# PROM.net
KiCad netlist of a schematic drawn in Altium Designer
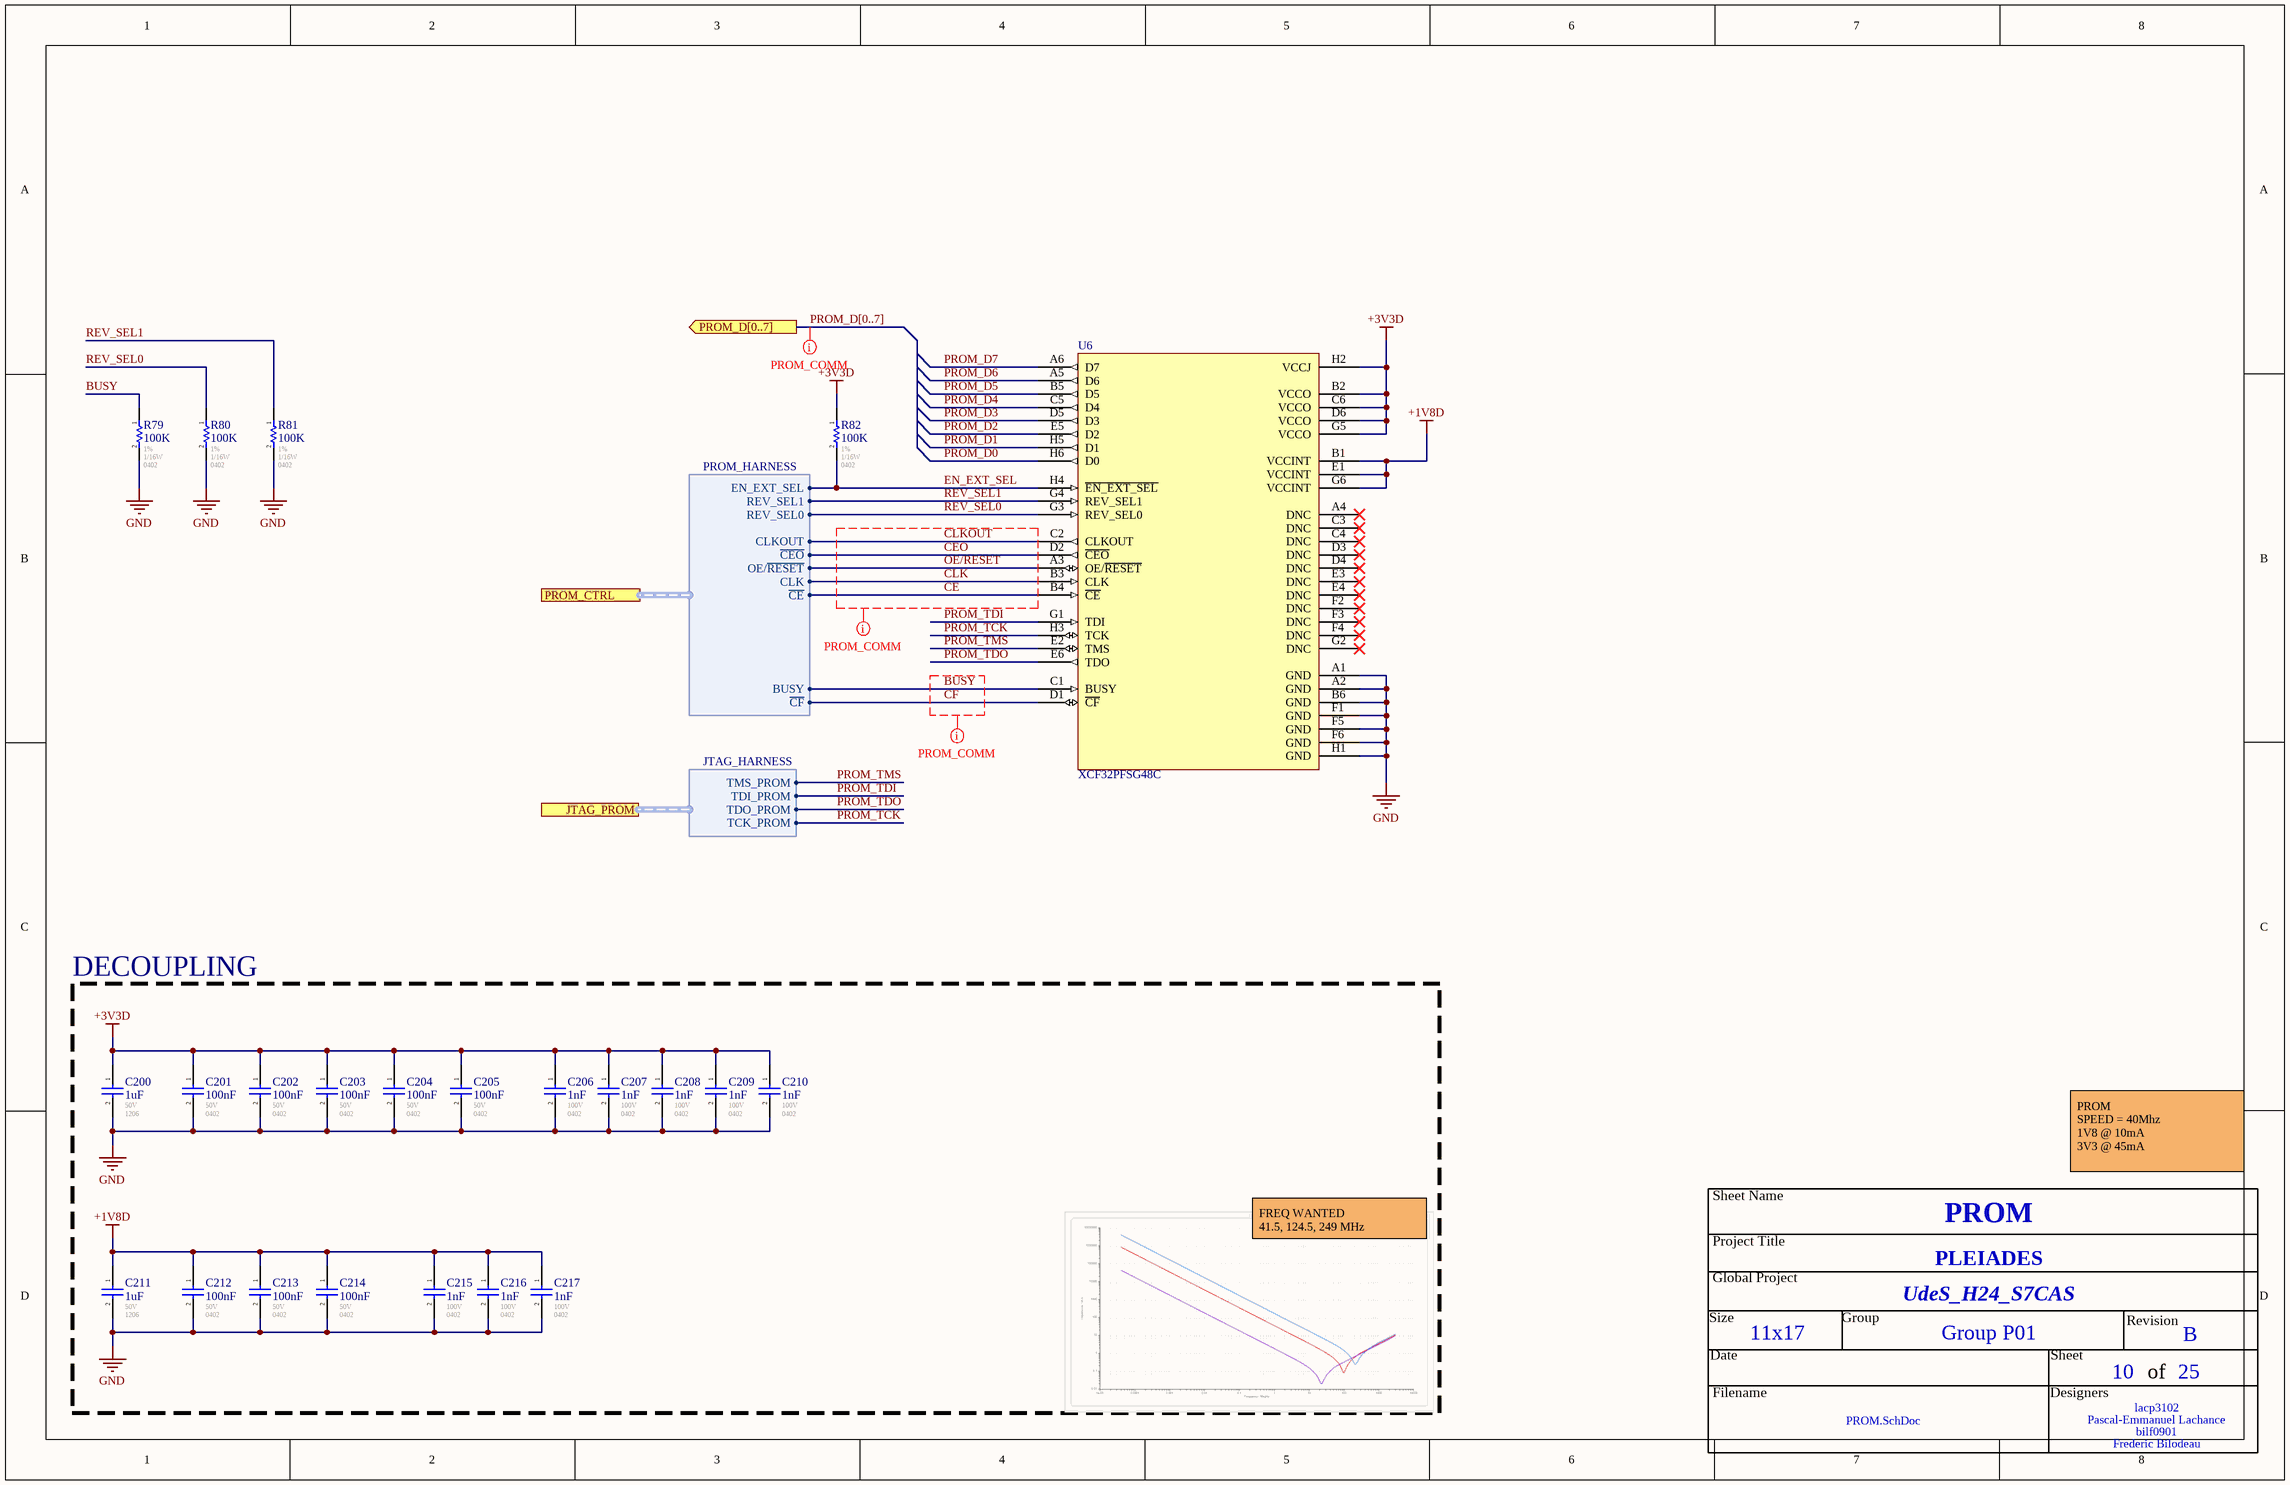
[diagram p0: PROM.SchDoc]

(export (version "E")
  (design (tool "Eeschema 10.0.6"))
  (components
    (comp (ref "C200")
      (value "1uF")
      (footprint "1206")
      (description "GCJ31CR71H105KA12L\r\n1206 1uF 10% X7R Ceramic Capacitor")
      (fields
        (field (name "MFR") "Murata")
        (field (name "PART#") "GCJ31CR71H105KA12L")
        (field (name "VOLTAGE - RATED") "50V")
      )
      (libsource (lib "Symbols") (part "CAP_CER"))
    )
    (comp (ref "C201")
      (value "100nF")
      (footprint "0402")
      (description "GCM155R71H104KE02J\r\n0402 100nF 10% X7R Ceramic Capacitor")
      (fields
        (field (name "MFR") "Murata")
        (field (name "PART#") "GCM155R71H104KE02J")
        (field (name "VOLTAGE - RATED") "50V")
      )
      (libsource (lib "Symbols") (part "CAP_CER"))
    )
    (comp (ref "C202")
      (value "100nF")
      (footprint "0402")
      (description "GCM155R71H104KE02J\r\n0402 100nF 10% X7R Ceramic Capacitor")
      (fields
        (field (name "MFR") "Murata")
        (field (name "PART#") "GCM155R71H104KE02J")
        (field (name "VOLTAGE - RATED") "50V")
      )
      (libsource (lib "Symbols") (part "CAP_CER"))
    )
    (comp (ref "C203")
      (value "100nF")
      (footprint "0402")
      (description "GCM155R71H104KE02J\r\n0402 100nF 10% X7R Ceramic Capacitor")
      (fields
        (field (name "MFR") "Murata")
        (field (name "PART#") "GCM155R71H104KE02J")
        (field (name "VOLTAGE - RATED") "50V")
      )
      (libsource (lib "Symbols") (part "CAP_CER"))
    )
    (comp (ref "C204")
      (value "100nF")
      (footprint "0402")
      (description "GCM155R71H104KE02J\r\n0402 100nF 10% X7R Ceramic Capacitor")
      (fields
        (field (name "MFR") "Murata")
        (field (name "PART#") "GCM155R71H104KE02J")
        (field (name "VOLTAGE - RATED") "50V")
      )
      (libsource (lib "Symbols") (part "CAP_CER"))
    )
    (comp (ref "C205")
      (value "100nF")
      (footprint "0402")
      (description "GCM155R71H104KE02J\r\n0402 100nF 10% X7R Ceramic Capacitor")
      (fields
        (field (name "MFR") "Murata")
        (field (name "PART#") "GCM155R71H104KE02J")
        (field (name "VOLTAGE - RATED") "50V")
      )
      (libsource (lib "Symbols") (part "CAP_CER"))
    )
    (comp (ref "C206")
      (value "1nF")
      (footprint "0402")
      (description "GCM155R72A102KA37D\r\n0402 1nF 10% X7R Ceramic Capacitor")
      (fields
        (field (name "MFR") "Murata")
        (field (name "PART#") "GCM155R72A102KA37D")
        (field (name "VOLTAGE - RATED") "100V")
      )
      (libsource (lib "Symbols") (part "CAP_CER"))
    )
    (comp (ref "C207")
      (value "1nF")
      (footprint "0402")
      (description "GCM155R72A102KA37D\r\n0402 1nF 10% X7R Ceramic Capacitor")
      (fields
        (field (name "MFR") "Murata")
        (field (name "PART#") "GCM155R72A102KA37D")
        (field (name "VOLTAGE - RATED") "100V")
      )
      (libsource (lib "Symbols") (part "CAP_CER"))
    )
    (comp (ref "C208")
      (value "1nF")
      (footprint "0402")
      (description "GCM155R72A102KA37D\r\n0402 1nF 10% X7R Ceramic Capacitor")
      (fields
        (field (name "MFR") "Murata")
        (field (name "PART#") "GCM155R72A102KA37D")
        (field (name "VOLTAGE - RATED") "100V")
      )
      (libsource (lib "Symbols") (part "CAP_CER"))
    )
    (comp (ref "C209")
      (value "1nF")
      (footprint "0402")
      (description "GCM155R72A102KA37D\r\n0402 1nF 10% X7R Ceramic Capacitor")
      (fields
        (field (name "MFR") "Murata")
        (field (name "PART#") "GCM155R72A102KA37D")
        (field (name "VOLTAGE - RATED") "100V")
      )
      (libsource (lib "Symbols") (part "CAP_CER"))
    )
    (comp (ref "C210")
      (value "1nF")
      (footprint "0402")
      (description "GCM155R72A102KA37D\r\n0402 1nF 10% X7R Ceramic Capacitor")
      (fields
        (field (name "MFR") "Murata")
        (field (name "PART#") "GCM155R72A102KA37D")
        (field (name "VOLTAGE - RATED") "100V")
      )
      (libsource (lib "Symbols") (part "CAP_CER"))
    )
    (comp (ref "C211")
      (value "1uF")
      (footprint "1206")
      (description "GCJ31CR71H105KA12L\r\n1206 1uF 10% X7R Ceramic Capacitor")
      (fields
        (field (name "MFR") "Murata")
        (field (name "PART#") "GCJ31CR71H105KA12L")
        (field (name "VOLTAGE - RATED") "50V")
      )
      (libsource (lib "Symbols") (part "CAP_CER"))
    )
    (comp (ref "C212")
      (value "100nF")
      (footprint "0402")
      (description "GCM155R71H104KE02J\r\n0402 100nF 10% X7R Ceramic Capacitor")
      (fields
        (field (name "MFR") "Murata")
        (field (name "PART#") "GCM155R71H104KE02J")
        (field (name "VOLTAGE - RATED") "50V")
      )
      (libsource (lib "Symbols") (part "CAP_CER"))
    )
    (comp (ref "C213")
      (value "100nF")
      (footprint "0402")
      (description "GCM155R71H104KE02J\r\n0402 100nF 10% X7R Ceramic Capacitor")
      (fields
        (field (name "MFR") "Murata")
        (field (name "PART#") "GCM155R71H104KE02J")
        (field (name "VOLTAGE - RATED") "50V")
      )
      (libsource (lib "Symbols") (part "CAP_CER"))
    )
    (comp (ref "C214")
      (value "100nF")
      (footprint "0402")
      (description "GCM155R71H104KE02J\r\n0402 100nF 10% X7R Ceramic Capacitor")
      (fields
        (field (name "MFR") "Murata")
        (field (name "PART#") "GCM155R71H104KE02J")
        (field (name "VOLTAGE - RATED") "50V")
      )
      (libsource (lib "Symbols") (part "CAP_CER"))
    )
    (comp (ref "C215")
      (value "1nF")
      (footprint "0402")
      (description "GCM155R72A102KA37D\r\n0402 1nF 10% X7R Ceramic Capacitor")
      (fields
        (field (name "MFR") "Murata")
        (field (name "PART#") "GCM155R72A102KA37D")
        (field (name "VOLTAGE - RATED") "100V")
      )
      (libsource (lib "Symbols") (part "CAP_CER"))
    )
    (comp (ref "C216")
      (value "1nF")
      (footprint "0402")
      (description "GCM155R72A102KA37D\r\n0402 1nF 10% X7R Ceramic Capacitor")
      (fields
        (field (name "MFR") "Murata")
        (field (name "PART#") "GCM155R72A102KA37D")
        (field (name "VOLTAGE - RATED") "100V")
      )
      (libsource (lib "Symbols") (part "CAP_CER"))
    )
    (comp (ref "C217")
      (value "1nF")
      (footprint "0402")
      (description "GCM155R72A102KA37D\r\n0402 1nF 10% X7R Ceramic Capacitor")
      (fields
        (field (name "MFR") "Murata")
        (field (name "PART#") "GCM155R72A102KA37D")
        (field (name "VOLTAGE - RATED") "100V")
      )
      (libsource (lib "Symbols") (part "CAP_CER"))
    )
    (comp (ref "R79")
      (value "100K")
      (footprint "RES_0402")
      (fields
        (field (name "TOLERANCE") "1%")
        (field (name "POWER") "1/16W")
        (field (name "PACKAGE / CASE") "0402")
      )
      (libsource (lib "Symbols") (part "RESISTOR"))
    )
    (comp (ref "R80")
      (value "100K")
      (footprint "RES_0402")
      (fields
        (field (name "TOLERANCE") "1%")
        (field (name "POWER") "1/16W")
        (field (name "PACKAGE / CASE") "0402")
      )
      (libsource (lib "Symbols") (part "RESISTOR"))
    )
    (comp (ref "R81")
      (value "100K")
      (footprint "RES_0402")
      (fields
        (field (name "TOLERANCE") "1%")
        (field (name "POWER") "1/16W")
        (field (name "PACKAGE / CASE") "0402")
      )
      (libsource (lib "Symbols") (part "RESISTOR"))
    )
    (comp (ref "R82")
      (value "100K")
      (footprint "RES_0402")
      (fields
        (field (name "TOLERANCE") "1%")
        (field (name "POWER") "1/16W")
        (field (name "PACKAGE / CASE") "0402")
      )
      (libsource (lib "Symbols") (part "RESISTOR"))
    )
    (comp (ref "U6")
      (value "XCF32PFSG48C")
      (footprint "TFBGA-48_0.8MM_8X9")
      (description "IC PROM SRL/PAR 1.8V 32M 48CSBGA")
      (fields (field (name "MFR") "Xilinx"))
      (libsource (lib "Misc") (part "XCF32PFSG48C"))
    )
  )
  (nets
    (net (code "3") (name "+1V8D") (class "Default")
      (node (ref "C211") (pin "1") (pinfunction "1_1") (pintype "passive"))
      (node (ref "C212") (pin "1") (pinfunction "1_1") (pintype "passive"))
      (node (ref "C213") (pin "1") (pinfunction "1_1") (pintype "passive"))
      (node (ref "C214") (pin "1") (pinfunction "1_1") (pintype "passive"))
      (node (ref "C215") (pin "1") (pinfunction "1_1") (pintype "passive"))
      (node (ref "C216") (pin "1") (pinfunction "1_1") (pintype "passive"))
      (node (ref "C217") (pin "1") (pinfunction "1_1") (pintype "passive"))
      (node (ref "U6") (pin "B1") (pinfunction "VCCINT_B1") (pintype "power_in"))
      (node (ref "U6") (pin "E1") (pinfunction "VCCINT_E1") (pintype "power_in"))
      (node (ref "U6") (pin "G6") (pinfunction "VCCINT_G6") (pintype "power_in"))
    )
    (net (code "4") (name "+3V3D") (class "Default")
      (node (ref "C200") (pin "1") (pinfunction "1_1") (pintype "passive"))
      (node (ref "C201") (pin "1") (pinfunction "1_1") (pintype "passive"))
      (node (ref "C202") (pin "1") (pinfunction "1_1") (pintype "passive"))
      (node (ref "C203") (pin "1") (pinfunction "1_1") (pintype "passive"))
      (node (ref "C204") (pin "1") (pinfunction "1_1") (pintype "passive"))
      (node (ref "C205") (pin "1") (pinfunction "1_1") (pintype "passive"))
      (node (ref "C206") (pin "1") (pinfunction "1_1") (pintype "passive"))
      (node (ref "C207") (pin "1") (pinfunction "1_1") (pintype "passive"))
      (node (ref "C208") (pin "1") (pinfunction "1_1") (pintype "passive"))
      (node (ref "C209") (pin "1") (pinfunction "1_1") (pintype "passive"))
      (node (ref "C210") (pin "1") (pinfunction "1_1") (pintype "passive"))
      (node (ref "R82") (pin "1") (pinfunction "1_1") (pintype "passive"))
      (node (ref "U6") (pin "B2") (pinfunction "VCCO_B2") (pintype "power_in"))
      (node (ref "U6") (pin "C6") (pinfunction "VCCO_C6") (pintype "power_in"))
      (node (ref "U6") (pin "D6") (pinfunction "VCCO_D6") (pintype "power_in"))
      (node (ref "U6") (pin "G5") (pinfunction "VCCO_G5") (pintype "power_in"))
      (node (ref "U6") (pin "H2") (pinfunction "VCCJ_H2") (pintype "power_in"))
    )
    (net (code "5") (name "/BUSY") (class "Default")
      (node (ref "R79") (pin "1") (pinfunction "1_1") (pintype "passive"))
      (node (ref "U6") (pin "C1") (pinfunction "BUSY_C1") (pintype "input"))
    )
    (net (code "6") (name "/CE") (class "Default")
      (node (ref "U6") (pin "B4") (pinfunction "CE_B4") (pintype "input"))
    )
    (net (code "7") (name "/CEO") (class "Default")
      (node (ref "U6") (pin "D2") (pinfunction "CEO_D2") (pintype "output"))
    )
    (net (code "8") (name "/CF") (class "Default")
      (node (ref "U6") (pin "D1") (pinfunction "CF_D1") (pintype "bidirectional"))
    )
    (net (code "9") (name "/CLK") (class "Default")
      (node (ref "U6") (pin "B3") (pinfunction "CLK_B3") (pintype "input"))
    )
    (net (code "10") (name "/CLKOUT") (class "Default")
      (node (ref "U6") (pin "C2") (pinfunction "CLKOUT_C2") (pintype "output"))
    )
    (net (code "11") (name "/EN_EXT_SEL") (class "Default")
      (node (ref "R82") (pin "2") (pinfunction "2_2") (pintype "passive"))
      (node (ref "U6") (pin "H4") (pinfunction "EN_EXT_SEL_H4") (pintype "input"))
    )
    (net (code "12") (name "/OE{slash}RESET") (class "Default")
      (node (ref "U6") (pin "A3") (pinfunction "OE/~{RESET}_A3") (pintype "bidirectional"))
    )
    (net (code "13") (name "/PROM_D0") (class "Default")
      (node (ref "U6") (pin "H6") (pinfunction "D0_H6") (pintype "output"))
    )
    (net (code "14") (name "/PROM_D1") (class "Default")
      (node (ref "U6") (pin "H5") (pinfunction "D1_H5") (pintype "output"))
    )
    (net (code "15") (name "/PROM_D2") (class "Default")
      (node (ref "U6") (pin "E5") (pinfunction "D2_E5") (pintype "output"))
    )
    (net (code "16") (name "/PROM_D3") (class "Default")
      (node (ref "U6") (pin "D5") (pinfunction "D3_D5") (pintype "output"))
    )
    (net (code "17") (name "/PROM_D4") (class "Default")
      (node (ref "U6") (pin "C5") (pinfunction "D4_C5") (pintype "output"))
    )
    (net (code "18") (name "/PROM_D5") (class "Default")
      (node (ref "U6") (pin "B5") (pinfunction "D5_B5") (pintype "output"))
    )
    (net (code "19") (name "/PROM_D6") (class "Default")
      (node (ref "U6") (pin "A5") (pinfunction "D6_A5") (pintype "output"))
    )
    (net (code "20") (name "/PROM_D7") (class "Default")
      (node (ref "U6") (pin "A6") (pinfunction "D7_A6") (pintype "output"))
    )
    (net (code "22") (name "/PROM_TCK") (class "Default")
      (node (ref "U6") (pin "H3") (pinfunction "TCK_H3") (pintype "bidirectional"))
    )
    (net (code "23") (name "/PROM_TDI") (class "Default")
      (node (ref "U6") (pin "G1") (pinfunction "TDI_G1") (pintype "input"))
    )
    (net (code "24") (name "/PROM_TDO") (class "Default")
      (node (ref "U6") (pin "E6") (pinfunction "TDO_E6") (pintype "output"))
    )
    (net (code "25") (name "/PROM_TMS") (class "Default")
      (node (ref "U6") (pin "E2") (pinfunction "TMS_E2") (pintype "bidirectional"))
    )
    (net (code "26") (name "/REV_SEL0") (class "Default")
      (node (ref "R80") (pin "1") (pinfunction "1_1") (pintype "passive"))
      (node (ref "U6") (pin "G3") (pinfunction "REV_SEL0_G3") (pintype "input"))
    )
    (net (code "27") (name "/REV_SEL1") (class "Default")
      (node (ref "R81") (pin "1") (pinfunction "1_1") (pintype "passive"))
      (node (ref "U6") (pin "G4") (pinfunction "REV_SEL1_G4") (pintype "input"))
    )
    (net (code "30") (name "GND") (class "Default")
      (node (ref "C200") (pin "2") (pinfunction "2_2") (pintype "passive"))
      (node (ref "C201") (pin "2") (pinfunction "2_2") (pintype "passive"))
      (node (ref "C202") (pin "2") (pinfunction "2_2") (pintype "passive"))
      (node (ref "C203") (pin "2") (pinfunction "2_2") (pintype "passive"))
      (node (ref "C204") (pin "2") (pinfunction "2_2") (pintype "passive"))
      (node (ref "C205") (pin "2") (pinfunction "2_2") (pintype "passive"))
      (node (ref "C206") (pin "2") (pinfunction "2_2") (pintype "passive"))
      (node (ref "C207") (pin "2") (pinfunction "2_2") (pintype "passive"))
      (node (ref "C208") (pin "2") (pinfunction "2_2") (pintype "passive"))
      (node (ref "C209") (pin "2") (pinfunction "2_2") (pintype "passive"))
      (node (ref "C210") (pin "2") (pinfunction "2_2") (pintype "passive"))
      (node (ref "C211") (pin "2") (pinfunction "2_2") (pintype "passive"))
      (node (ref "C212") (pin "2") (pinfunction "2_2") (pintype "passive"))
      (node (ref "C213") (pin "2") (pinfunction "2_2") (pintype "passive"))
      (node (ref "C214") (pin "2") (pinfunction "2_2") (pintype "passive"))
      (node (ref "C215") (pin "2") (pinfunction "2_2") (pintype "passive"))
      (node (ref "C216") (pin "2") (pinfunction "2_2") (pintype "passive"))
      (node (ref "C217") (pin "2") (pinfunction "2_2") (pintype "passive"))
      (node (ref "R79") (pin "2") (pinfunction "2_2") (pintype "passive"))
      (node (ref "R80") (pin "2") (pinfunction "2_2") (pintype "passive"))
      (node (ref "R81") (pin "2") (pinfunction "2_2") (pintype "passive"))
      (node (ref "U6") (pin "A1") (pinfunction "GND_A1") (pintype "power_in"))
      (node (ref "U6") (pin "A2") (pinfunction "GND_A2") (pintype "power_in"))
      (node (ref "U6") (pin "B6") (pinfunction "GND_B6") (pintype "power_in"))
      (node (ref "U6") (pin "F1") (pinfunction "GND_F1") (pintype "power_in"))
      (node (ref "U6") (pin "F5") (pinfunction "GND_F5") (pintype "power_in"))
      (node (ref "U6") (pin "F6") (pinfunction "GND_F6") (pintype "power_in"))
      (node (ref "U6") (pin "H1") (pinfunction "GND_H1") (pintype "power_in"))
    )
    (net (code "31") (name "unconnected-(U6-DNC-PadA4)") (class "Default")
      (node (ref "U6") (pin "A4") (pinfunction "DNC_A4") (pintype "passive+no_connect"))
    )
    (net (code "32") (name "unconnected-(U6-DNC-PadC3)") (class "Default")
      (node (ref "U6") (pin "C3") (pinfunction "DNC_C3") (pintype "passive+no_connect"))
    )
    (net (code "33") (name "unconnected-(U6-DNC-PadC4)") (class "Default")
      (node (ref "U6") (pin "C4") (pinfunction "DNC_C4") (pintype "passive+no_connect"))
    )
    (net (code "34") (name "unconnected-(U6-DNC-PadD3)") (class "Default")
      (node (ref "U6") (pin "D3") (pinfunction "DNC_D3") (pintype "passive+no_connect"))
    )
    (net (code "35") (name "unconnected-(U6-DNC-PadD4)") (class "Default")
      (node (ref "U6") (pin "D4") (pinfunction "DNC_D4") (pintype "passive+no_connect"))
    )
    (net (code "36") (name "unconnected-(U6-DNC-PadE3)") (class "Default")
      (node (ref "U6") (pin "E3") (pinfunction "DNC_E3") (pintype "passive+no_connect"))
    )
    (net (code "37") (name "unconnected-(U6-DNC-PadE4)") (class "Default")
      (node (ref "U6") (pin "E4") (pinfunction "DNC_E4") (pintype "passive+no_connect"))
    )
    (net (code "38") (name "unconnected-(U6-DNC-PadF2)") (class "Default")
      (node (ref "U6") (pin "F2") (pinfunction "DNC_F2") (pintype "passive+no_connect"))
    )
    (net (code "39") (name "unconnected-(U6-DNC-PadF3)") (class "Default")
      (node (ref "U6") (pin "F3") (pinfunction "DNC_F3") (pintype "passive+no_connect"))
    )
    (net (code "40") (name "unconnected-(U6-DNC-PadF4)") (class "Default")
      (node (ref "U6") (pin "F4") (pinfunction "DNC_F4") (pintype "passive+no_connect"))
    )
    (net (code "41") (name "unconnected-(U6-DNC-PadG2)") (class "Default")
      (node (ref "U6") (pin "G2") (pinfunction "DNC_G2") (pintype "passive+no_connect"))
    )
  )
)
